# 0301_LTC6820_chip.net
KiCad netlist of a schematic drawn in Altium Designer
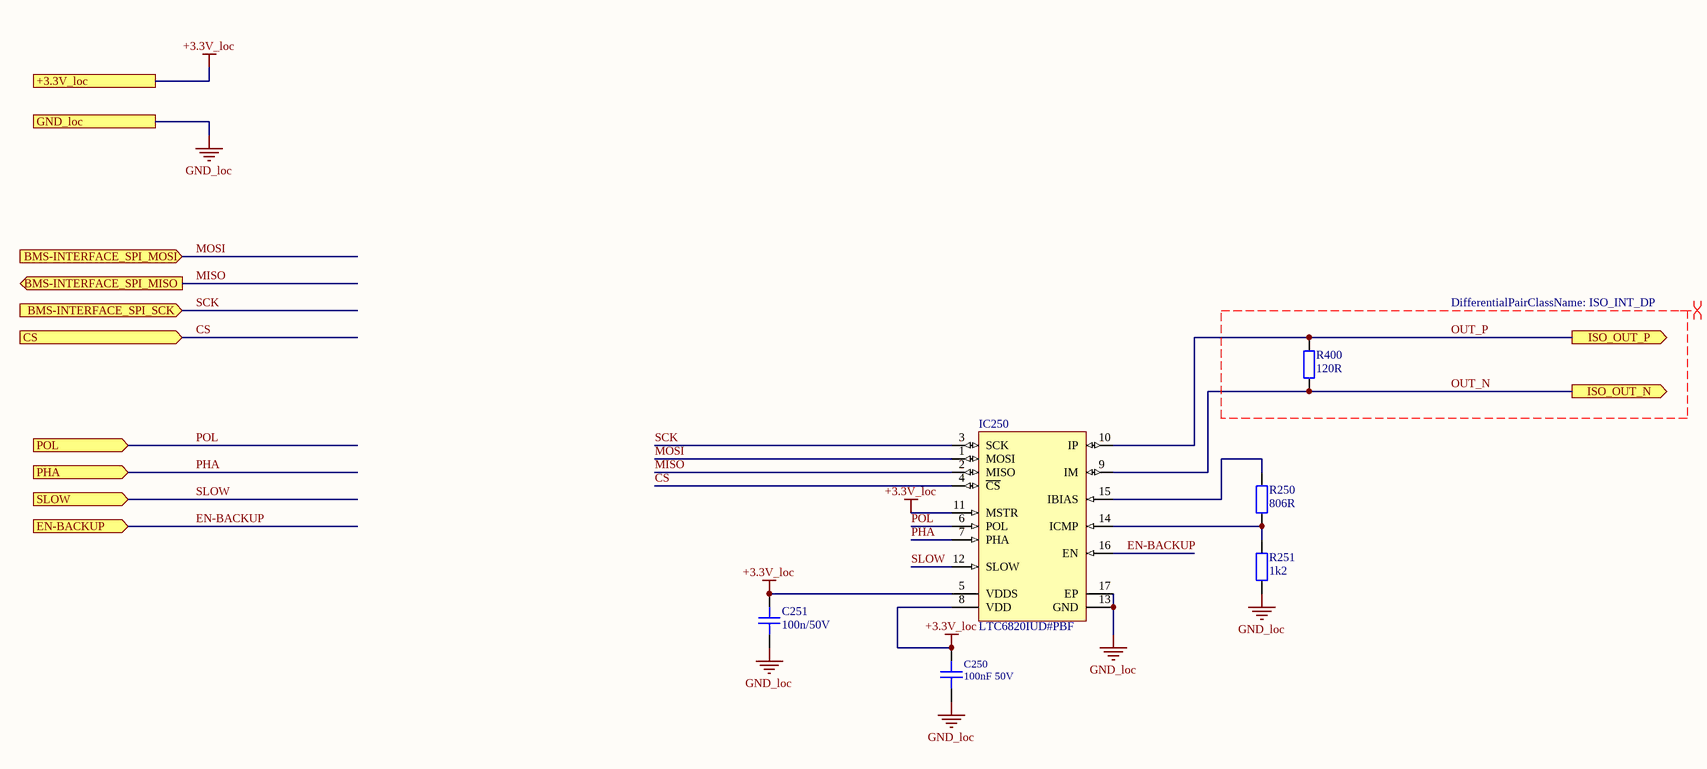
[diagram p0: 0301_LTC6820_chip.SchDoc]

(export (version "E")
  (design (tool "Eeschema 10.0.6"))
  (components
    (comp (ref "C250")
      (value "100nF 50V")
      (footprint "0603C")
      (description "Ceramic, 100nF, ±10%, 50V, X7R, –55 to 125°C, 0603 (1608),RoHS, Automotive")
      (fields (field (name "PART NUMBER") "GCJ188R71H104KA12") (field (name "TOLERANCE") "±10%"))
      (libsource (lib "master-010106") (part "gen_C_ceramic_100n_50V_X7R_0603"))
    )
    (comp (ref "C251")
      (value "100n/50V")
      (footprint "0603C")
      (description "MLCC")
      (fields (field (name "PART NUMBER") "gen_C_ceramic_100n_50V_X7R_0603"))
      (libsource (lib "master-010106") (part "C"))
    )
    (comp (ref "IC250")
      (value "LTC6820IUD#PBF")
      (footprint "LT-UD-16-EPV-AA_L")
      (fields (field (name "MANUFACTURER") "Linear Technology"))
      (libsource (lib "Altium Content Vault") (part "LT-LTC6820-UD-16"))
    )
    (comp (ref "R250")
      (value "806R")
      (footprint "0603R")
      (description "SMD Resistor 806R 0603")
      (fields (field (name "PART NUMBER") "gen_R_806R_0603") (field (name "TOLERANCE") "1%"))
      (libsource (lib "master-010106") (part "R"))
    )
    (comp (ref "R251")
      (value "1k2")
      (footprint "0603R")
      (description "SMD Resistor 1k2 0603")
      (fields (field (name "PART NUMBER") "gen_R_1k2_0603") (field (name "TOLERANCE") "1%"))
      (libsource (lib "master-010106") (part "R"))
    )
    (comp (ref "R400")
      (value "120R")
      (footprint "0603R")
      (description "SMD Resistor 120R 0603")
      (fields (field (name "PART NUMBER") "gen_R_120R_0603") (field (name "TOLERANCE") "1%"))
      (libsource (lib "OE750") (part "R"))
    )
  )
  (nets
    (net (code "1") (name "+3.3V_loc") (class "Default")
      (node (ref "C250") (pin "2") (pinfunction "2_2") (pintype "passive"))
      (node (ref "C251") (pin "2") (pinfunction "2_2") (pintype "passive"))
      (node (ref "IC250") (pin "11") (pinfunction "MSTR_11") (pintype "input"))
      (node (ref "IC250") (pin "5") (pinfunction "VDDS_5") (pintype "power_in"))
      (node (ref "IC250") (pin "8") (pinfunction "VDD_8") (pintype "power_in"))
    )
    (net (code "2") (name "/CS") (class "Default")
      (node (ref "IC250") (pin "4") (pinfunction "~{CS}_4") (pintype "bidirectional"))
    )
    (net (code "3") (name "/EN-BACKUP") (class "Default")
      (node (ref "IC250") (pin "16") (pinfunction "EN_16") (pintype "input"))
    )
    (net (code "4") (name "/MISO") (class "Default")
      (node (ref "IC250") (pin "2") (pinfunction "MISO_2") (pintype "bidirectional"))
    )
    (net (code "5") (name "/MOSI") (class "Default")
      (node (ref "IC250") (pin "1") (pinfunction "MOSI_1") (pintype "bidirectional"))
    )
    (net (code "6") (name "/OUT_N") (class "Default")
      (node (ref "IC250") (pin "9") (pinfunction "IM_9") (pintype "bidirectional"))
      (node (ref "R400") (pin "1") (pinfunction "1_1") (pintype "passive"))
    )
    (net (code "7") (name "/OUT_P") (class "Default")
      (node (ref "IC250") (pin "10") (pinfunction "IP_10") (pintype "bidirectional"))
      (node (ref "R400") (pin "2") (pinfunction "2_2") (pintype "passive"))
    )
    (net (code "8") (name "/PHA") (class "Default")
      (node (ref "IC250") (pin "7") (pinfunction "PHA_7") (pintype "input"))
    )
    (net (code "9") (name "/POL") (class "Default")
      (node (ref "IC250") (pin "6") (pinfunction "POL_6") (pintype "input"))
    )
    (net (code "10") (name "/SCK") (class "Default")
      (node (ref "IC250") (pin "3") (pinfunction "SCK_3") (pintype "bidirectional"))
    )
    (net (code "11") (name "/SLOW") (class "Default")
      (node (ref "IC250") (pin "12") (pinfunction "SLOW_12") (pintype "input"))
    )
    (net (code "12") (name "GND_loc") (class "Default")
      (node (ref "C250") (pin "1") (pinfunction "1_1") (pintype "passive"))
      (node (ref "C251") (pin "1") (pinfunction "1_1") (pintype "passive"))
      (node (ref "IC250") (pin "13") (pinfunction "GND_13") (pintype "power_in"))
      (node (ref "IC250") (pin "17") (pinfunction "EP_17") (pintype "power_in"))
      (node (ref "R251") (pin "1") (pinfunction "1_1") (pintype "passive"))
    )
    (net (code "13") (name "Net-(IC250-IBIAS)") (class "Default")
      (node (ref "IC250") (pin "15") (pinfunction "IBIAS_15") (pintype "input"))
      (node (ref "R250") (pin "2") (pinfunction "2_2") (pintype "passive"))
    )
    (net (code "14") (name "Net-(IC250-ICMP)") (class "Default")
      (node (ref "IC250") (pin "14") (pinfunction "ICMP_14") (pintype "input"))
      (node (ref "R250") (pin "1") (pinfunction "1_1") (pintype "passive"))
      (node (ref "R251") (pin "2") (pinfunction "2_2") (pintype "passive"))
    )
  )
)
